# V3_0.net
KiCad netlist of a schematic drawn in EAGLE
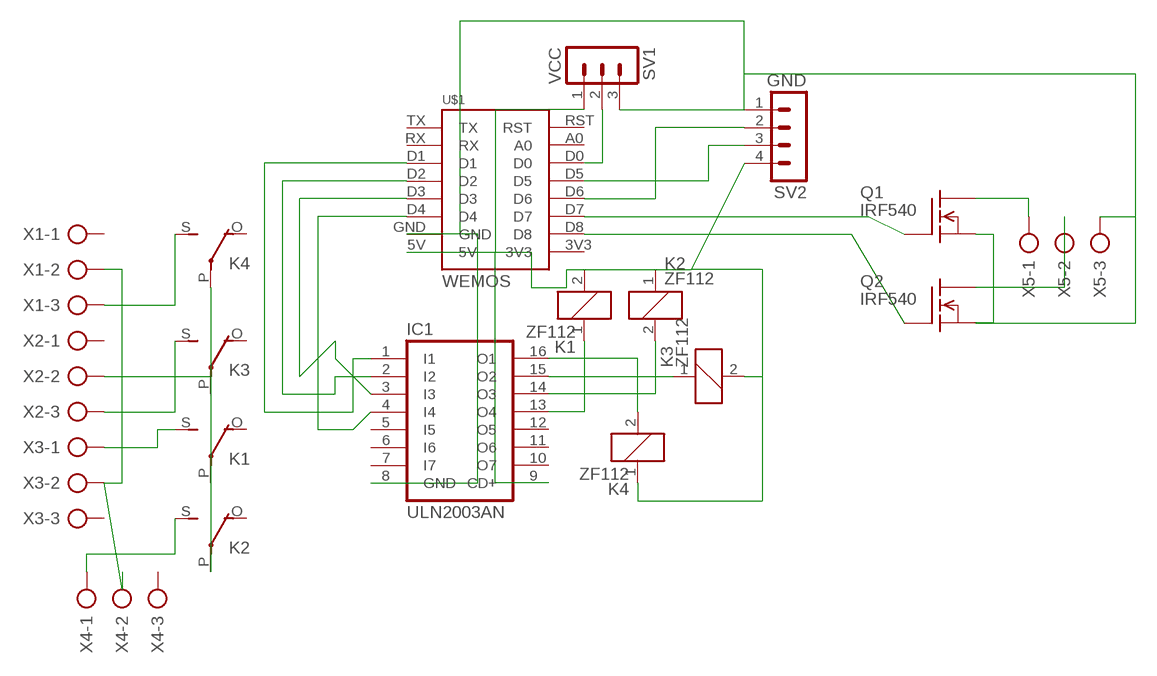
[diagram p0: schematic, sheet 1]

(export (version "E")
  (design (tool "Eeschema 10.0.6"))
  (components
    (comp (ref "IC1")
      (value "ULN2003AN")
      (footprint "eagle-import:DIL16")
      (libsource (lib "eagle-import") (part "ULN2003AN"))
    )
    (comp (ref "K1")
      (value "ZF112")
      (footprint "eagle-import:ZF112")
      (libsource (lib "eagle-import") (part "ZF112"))
    )
    (comp (ref "K2")
      (value "ZF112")
      (footprint "eagle-import:ZF112")
      (libsource (lib "eagle-import") (part "ZF112"))
    )
    (comp (ref "K3")
      (value "ZF112")
      (footprint "eagle-import:ZF112")
      (libsource (lib "eagle-import") (part "ZF112"))
    )
    (comp (ref "K4")
      (value "ZF112")
      (footprint "eagle-import:ZF112")
      (libsource (lib "eagle-import") (part "ZF112"))
    )
    (comp (ref "Q1")
      (value "IRF540")
      (footprint "eagle-import:TO220")
      (libsource (lib "eagle-import") (part "IRF540"))
    )
    (comp (ref "Q2")
      (value "IRF540")
      (footprint "eagle-import:TO220")
      (libsource (lib "eagle-import") (part "IRF540"))
    )
    (comp (ref "SV1")
      (value "VCC")
      (footprint "eagle-import:MA03-1")
      (libsource (lib "eagle-import") (part "MA03-1"))
    )
    (comp (ref "SV2")
      (value "GND")
      (footprint "eagle-import:MA04-1")
      (libsource (lib "eagle-import") (part "MA04-1"))
    )
    (comp (ref "U$1")
      (value "WEMOS")
      (footprint "eagle-import:WEMOS")
      (libsource (lib "eagle-import") (part "WEMOS"))
    )
    (comp (ref "X1")
      (value "AK300/3")
      (footprint "eagle-import:AK300_3")
      (libsource (lib "eagle-import") (part "AK300/3"))
    )
    (comp (ref "X2")
      (value "AK300/3")
      (footprint "eagle-import:AK300_3")
      (libsource (lib "eagle-import") (part "AK300/3"))
    )
    (comp (ref "X3")
      (value "AK300/3")
      (footprint "eagle-import:AK300_3")
      (libsource (lib "eagle-import") (part "AK300/3"))
    )
    (comp (ref "X4")
      (value "AK300/3")
      (footprint "eagle-import:AK300_3")
      (libsource (lib "eagle-import") (part "AK300/3"))
    )
    (comp (ref "X5")
      (value "AK300/3")
      (footprint "eagle-import:AK300_3")
      (libsource (lib "eagle-import") (part "AK300/3"))
    )
  )
  (nets
    (net (code "1") (name "Net-(IC1-CD+)") (class "Default")
      (node (ref "IC1") (pin "9") (pinfunction "CD+_9") (pintype "passive"))
      (node (ref "K1") (pin "2") (pinfunction "2_2") (pintype "passive"))
      (node (ref "K2") (pin "1") (pinfunction "1_1") (pintype "passive"))
      (node (ref "K3") (pin "2") (pinfunction "2_2") (pintype "passive"))
      (node (ref "K4") (pin "1") (pinfunction "1_1") (pintype "passive"))
      (node (ref "SV1") (pin "1") (pinfunction "1_1") (pintype "passive"))
      (node (ref "SV2") (pin "4") (pinfunction "4_4") (pintype "passive"))
      (node (ref "U$1") (pin "5V") (pinfunction "5V_5V") (pintype "bidirectional"))
    )
    (net (code "2") (name "Net-(IC1-GND)") (class "Default")
      (node (ref "IC1") (pin "8") (pinfunction "GND_8") (pintype "power_in"))
      (node (ref "Q1") (pin "3") (pinfunction "S_3") (pintype "passive"))
      (node (ref "Q2") (pin "3") (pinfunction "S_3") (pintype "passive"))
      (node (ref "SV1") (pin "3") (pinfunction "3_3") (pintype "passive"))
      (node (ref "SV2") (pin "1") (pinfunction "1_1") (pintype "passive"))
      (node (ref "U$1") (pin "GND") (pinfunction "GND_GND") (pintype "bidirectional"))
      (node (ref "X5") (pin "3") (pinfunction "KL_3") (pintype "passive"))
    )
    (net (code "3") (name "Net-(IC1-I1)") (class "Default")
      (node (ref "IC1") (pin "1") (pinfunction "I1_1") (pintype "input"))
      (node (ref "U$1") (pin "D1") (pinfunction "D1_D1") (pintype "bidirectional"))
    )
    (net (code "4") (name "Net-(IC1-I2)") (class "Default")
      (node (ref "IC1") (pin "2") (pinfunction "I2_2") (pintype "input"))
      (node (ref "U$1") (pin "D2") (pinfunction "D2_D2") (pintype "bidirectional"))
    )
    (net (code "5") (name "Net-(IC1-I3)") (class "Default")
      (node (ref "IC1") (pin "3") (pinfunction "I3_3") (pintype "input"))
      (node (ref "U$1") (pin "D3") (pinfunction "D3_D3") (pintype "bidirectional"))
    )
    (net (code "6") (name "Net-(IC1-I4)") (class "Default")
      (node (ref "IC1") (pin "4") (pinfunction "I4_4") (pintype "input"))
      (node (ref "U$1") (pin "D4") (pinfunction "D4_D4") (pintype "bidirectional"))
    )
    (net (code "7") (name "Net-(IC1-O1)") (class "Default")
      (node (ref "IC1") (pin "16") (pinfunction "O1_16") (pintype "open_collector"))
      (node (ref "K4") (pin "2") (pinfunction "2_2") (pintype "passive"))
    )
    (net (code "8") (name "Net-(IC1-O2)") (class "Default")
      (node (ref "IC1") (pin "15") (pinfunction "O2_15") (pintype "open_collector"))
      (node (ref "K3") (pin "1") (pinfunction "1_1") (pintype "passive"))
    )
    (net (code "9") (name "Net-(IC1-O3)") (class "Default")
      (node (ref "IC1") (pin "14") (pinfunction "O3_14") (pintype "open_collector"))
      (node (ref "K2") (pin "2") (pinfunction "2_2") (pintype "passive"))
    )
    (net (code "10") (name "Net-(IC1-O4)") (class "Default")
      (node (ref "IC1") (pin "13") (pinfunction "O4_13") (pintype "open_collector"))
      (node (ref "K1") (pin "1") (pinfunction "1_1") (pintype "passive"))
    )
    (net (code "11") (name "Net-(Q1-D)") (class "Default")
      (node (ref "Q1") (pin "2") (pinfunction "D_2") (pintype "passive"))
      (node (ref "X5") (pin "1") (pinfunction "KL_1") (pintype "passive"))
    )
    (net (code "12") (name "Net-(Q1-G)") (class "Default")
      (node (ref "Q1") (pin "1") (pinfunction "G_1") (pintype "passive"))
      (node (ref "U$1") (pin "D7") (pinfunction "D7_D7") (pintype "bidirectional"))
    )
    (net (code "13") (name "Net-(Q2-D)") (class "Default")
      (node (ref "Q2") (pin "2") (pinfunction "D_2") (pintype "passive"))
      (node (ref "X5") (pin "2") (pinfunction "KL_2") (pintype "passive"))
    )
    (net (code "14") (name "Net-(Q2-G)") (class "Default")
      (node (ref "Q2") (pin "1") (pinfunction "G_1") (pintype "passive"))
      (node (ref "U$1") (pin "D8") (pinfunction "D8_D8") (pintype "bidirectional"))
    )
    (net (code "15") (name "Net-(SV1-Pad2)") (class "Default")
      (node (ref "SV1") (pin "2") (pinfunction "2_2") (pintype "passive"))
      (node (ref "U$1") (pin "D0") (pinfunction "D0_D0") (pintype "bidirectional"))
    )
    (net (code "16") (name "Net-(SV2-Pad2)") (class "Default")
      (node (ref "SV2") (pin "2") (pinfunction "2_2") (pintype "passive"))
      (node (ref "U$1") (pin "D6") (pinfunction "D6_D6") (pintype "bidirectional"))
    )
    (net (code "17") (name "Net-(SV2-Pad3)") (class "Default")
      (node (ref "SV2") (pin "3") (pinfunction "3_3") (pintype "passive"))
      (node (ref "U$1") (pin "D5") (pinfunction "D5_D5") (pintype "bidirectional"))
    )
    (net (code "18") (name "Net-(X1B-KL)") (class "Default")
      (node (ref "K1") (pin "P") (pinfunction "P_P") (pintype "passive"))
      (node (ref "K2") (pin "P") (pinfunction "P_P") (pintype "passive"))
      (node (ref "K3") (pin "P") (pinfunction "P_P") (pintype "passive"))
      (node (ref "K4") (pin "P") (pinfunction "P_P") (pintype "passive"))
      (node (ref "X1") (pin "2") (pinfunction "KL_2") (pintype "passive"))
      (node (ref "X2") (pin "2") (pinfunction "KL_2") (pintype "passive"))
      (node (ref "X3") (pin "2") (pinfunction "KL_2") (pintype "passive"))
      (node (ref "X4") (pin "2") (pinfunction "KL_2") (pintype "passive"))
    )
    (net (code "19") (name "Net-(X1C-KL)") (class "Default")
      (node (ref "K4") (pin "S") (pinfunction "S_S") (pintype "passive"))
      (node (ref "X1") (pin "3") (pinfunction "KL_3") (pintype "passive"))
    )
    (net (code "20") (name "Net-(X2C-KL)") (class "Default")
      (node (ref "K3") (pin "S") (pinfunction "S_S") (pintype "passive"))
      (node (ref "X2") (pin "3") (pinfunction "KL_3") (pintype "passive"))
    )
    (net (code "21") (name "Net-(X3A-KL)") (class "Default")
      (node (ref "K1") (pin "S") (pinfunction "S_S") (pintype "passive"))
      (node (ref "X3") (pin "1") (pinfunction "KL_1") (pintype "passive"))
    )
    (net (code "22") (name "Net-(X4A-KL)") (class "Default")
      (node (ref "K2") (pin "S") (pinfunction "S_S") (pintype "passive"))
      (node (ref "X4") (pin "1") (pinfunction "KL_1") (pintype "passive"))
    )
    (net (code "23") (name "unconnected-(IC1-I5-Pad5)") (class "Default")
      (node (ref "IC1") (pin "5") (pinfunction "I5_5") (pintype "input"))
    )
    (net (code "24") (name "unconnected-(IC1-I6-Pad6)") (class "Default")
      (node (ref "IC1") (pin "6") (pinfunction "I6_6") (pintype "input"))
    )
    (net (code "25") (name "unconnected-(IC1-I7-Pad7)") (class "Default")
      (node (ref "IC1") (pin "7") (pinfunction "I7_7") (pintype "input"))
    )
    (net (code "26") (name "unconnected-(IC1-O5-Pad12)") (class "Default")
      (node (ref "IC1") (pin "12") (pinfunction "O5_12") (pintype "open_collector"))
    )
    (net (code "27") (name "unconnected-(IC1-O6-Pad11)") (class "Default")
      (node (ref "IC1") (pin "11") (pinfunction "O6_11") (pintype "open_collector"))
    )
    (net (code "28") (name "unconnected-(IC1-O7-Pad10)") (class "Default")
      (node (ref "IC1") (pin "10") (pinfunction "O7_10") (pintype "open_collector"))
    )
    (net (code "29") (name "unconnected-(K1-PadO)") (class "Default")
      (node (ref "K1") (pin "O") (pinfunction "O_O") (pintype "passive"))
    )
    (net (code "30") (name "unconnected-(K2-PadO)") (class "Default")
      (node (ref "K2") (pin "O") (pinfunction "O_O") (pintype "passive"))
    )
    (net (code "31") (name "unconnected-(K3-PadO)") (class "Default")
      (node (ref "K3") (pin "O") (pinfunction "O_O") (pintype "passive"))
    )
    (net (code "32") (name "unconnected-(K4-PadO)") (class "Default")
      (node (ref "K4") (pin "O") (pinfunction "O_O") (pintype "passive"))
    )
    (net (code "33") (name "unconnected-(U$1-Pad3V3)") (class "Default")
      (node (ref "U$1") (pin "3V3") (pinfunction "3V3_3V3") (pintype "bidirectional"))
    )
    (net (code "34") (name "unconnected-(U$1-PadA0)") (class "Default")
      (node (ref "U$1") (pin "A0") (pinfunction "A0_A0") (pintype "bidirectional"))
    )
    (net (code "35") (name "unconnected-(U$1-PadRST)") (class "Default")
      (node (ref "U$1") (pin "RST") (pinfunction "RST_RST") (pintype "bidirectional"))
    )
    (net (code "36") (name "unconnected-(U$1-PadRX)") (class "Default")
      (node (ref "U$1") (pin "RX") (pinfunction "RX_RX") (pintype "bidirectional"))
    )
    (net (code "37") (name "unconnected-(U$1-PadTX)") (class "Default")
      (node (ref "U$1") (pin "TX") (pinfunction "TX_TX") (pintype "bidirectional"))
    )
    (net (code "38") (name "unconnected-(X1A-KL-Pad1)") (class "Default")
      (node (ref "X1") (pin "1") (pinfunction "KL_1") (pintype "passive"))
    )
    (net (code "39") (name "unconnected-(X2A-KL-Pad1)") (class "Default")
      (node (ref "X2") (pin "1") (pinfunction "KL_1") (pintype "passive"))
    )
    (net (code "40") (name "unconnected-(X3C-KL-Pad3)") (class "Default")
      (node (ref "X3") (pin "3") (pinfunction "KL_3") (pintype "passive"))
    )
    (net (code "41") (name "unconnected-(X4C-KL-Pad3)") (class "Default")
      (node (ref "X4") (pin "3") (pinfunction "KL_3") (pintype "passive"))
    )
  )
)
